# B311D.net
KiCad netlist of a schematic drawn in EAGLE
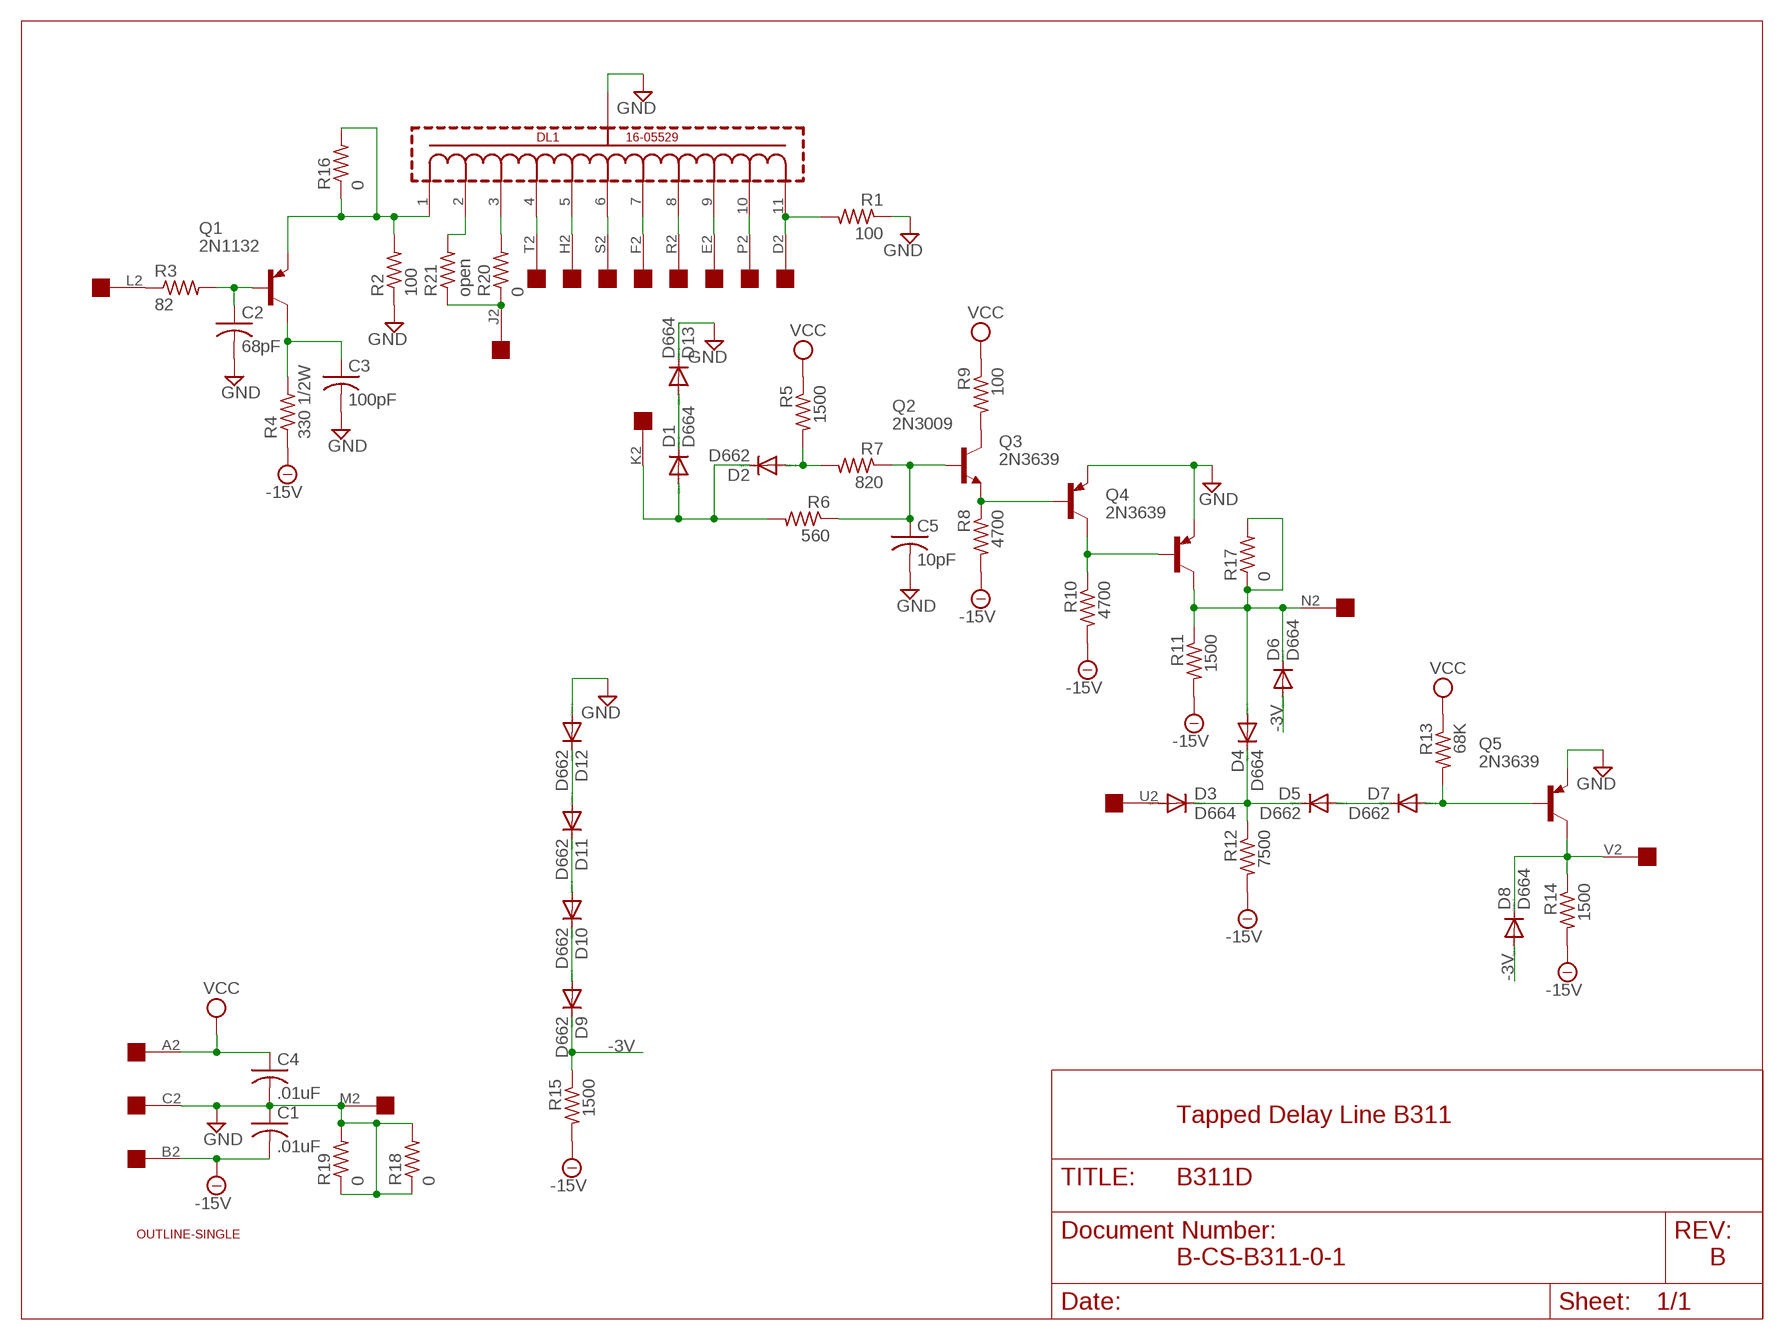
[diagram p0: schematic, sheet 1]

(export (version "E")
  (design (tool "Eeschema 10.0.6"))
  (components
    (comp (ref "C1")
      (value ".01uF")
      (footprint "eagle-import:C063-025X075")
      (libsource (lib "eagle-import") (part "C-US"))
    )
    (comp (ref "C2")
      (value "68pF")
      (footprint "eagle-import:C063-025X075")
      (libsource (lib "eagle-import") (part "C-US"))
    )
    (comp (ref "C3")
      (value "100pF")
      (footprint "eagle-import:C063-025X075")
      (libsource (lib "eagle-import") (part "C-US"))
    )
    (comp (ref "C4")
      (value ".01uF")
      (footprint "eagle-import:C063-025X075")
      (libsource (lib "eagle-import") (part "C-US"))
    )
    (comp (ref "C5")
      (value "10pF")
      (footprint "eagle-import:C063-025X075")
      (libsource (lib "eagle-import") (part "C-US"))
    )
    (comp (ref "D1")
      (value "D664")
      (footprint "eagle-import:DO35-10")
      (libsource (lib "eagle-import") (part "DIODE-DO35-10"))
    )
    (comp (ref "D2")
      (value "D662")
      (footprint "eagle-import:DO35-10")
      (libsource (lib "eagle-import") (part "DIODE-DO35-10"))
    )
    (comp (ref "D3")
      (value "D664")
      (footprint "eagle-import:DO35-10")
      (libsource (lib "eagle-import") (part "DIODE-DO35-10"))
    )
    (comp (ref "D4")
      (value "D664")
      (footprint "eagle-import:DO35-10")
      (libsource (lib "eagle-import") (part "DIODE-DO35-10"))
    )
    (comp (ref "D5")
      (value "D662")
      (footprint "eagle-import:DO35-10")
      (libsource (lib "eagle-import") (part "DIODE-DO35-10"))
    )
    (comp (ref "D6")
      (value "D664")
      (footprint "eagle-import:DO35-10")
      (libsource (lib "eagle-import") (part "DIODE-DO35-10"))
    )
    (comp (ref "D7")
      (value "D662")
      (footprint "eagle-import:DO35-10")
      (libsource (lib "eagle-import") (part "DIODE-DO35-10"))
    )
    (comp (ref "D8")
      (value "D664")
      (footprint "eagle-import:DO35-10")
      (libsource (lib "eagle-import") (part "DIODE-DO35-10"))
    )
    (comp (ref "D9")
      (value "D662")
      (footprint "eagle-import:DO35-10")
      (libsource (lib "eagle-import") (part "DIODE-DO35-10"))
    )
    (comp (ref "D10")
      (value "D662")
      (footprint "eagle-import:DO35-10")
      (libsource (lib "eagle-import") (part "DIODE-DO35-10"))
    )
    (comp (ref "D11")
      (value "D662")
      (footprint "eagle-import:DO35-10")
      (libsource (lib "eagle-import") (part "DIODE-DO35-10"))
    )
    (comp (ref "D12")
      (value "D662")
      (footprint "eagle-import:DO35-10")
      (libsource (lib "eagle-import") (part "DIODE-DO35-10"))
    )
    (comp (ref "D13")
      (value "D664")
      (footprint "eagle-import:DO35-10")
      (libsource (lib "eagle-import") (part "DIODE-DO35-10"))
    )
    (comp (ref "DL1")
      (value "16-05529")
      (footprint "eagle-import:16-05529")
      (libsource (lib "eagle-import") (part "16-05529"))
    )
    (comp (ref "Q1")
      (value "2N1132")
      (footprint "eagle-import:TO5")
      (libsource (lib "eagle-import") (part "-PNP-TO5"))
    )
    (comp (ref "Q2")
      (value "2N3009")
      (footprint "eagle-import:TO5")
      (libsource (lib "eagle-import") (part "-NPN-TO5"))
    )
    (comp (ref "Q3")
      (value "2N3639")
      (footprint "eagle-import:TO5")
      (libsource (lib "eagle-import") (part "-PNP-TO5"))
    )
    (comp (ref "Q4")
      (value "2N3639")
      (footprint "eagle-import:TO5")
      (libsource (lib "eagle-import") (part "-PNP-TO5"))
    )
    (comp (ref "Q5")
      (value "2N3639")
      (footprint "eagle-import:TO5")
      (libsource (lib "eagle-import") (part "-PNP-TO5"))
    )
    (comp (ref "R1")
      (value "100")
      (footprint "eagle-import:0207_10")
      (libsource (lib "eagle-import") (part "R-US_0207/10"))
    )
    (comp (ref "R2")
      (value "100")
      (footprint "eagle-import:0207_10")
      (libsource (lib "eagle-import") (part "R-US_0207/10"))
    )
    (comp (ref "R3")
      (value "82")
      (footprint "eagle-import:0207_10")
      (libsource (lib "eagle-import") (part "R-US_0207/10"))
    )
    (comp (ref "R4")
      (value "330 1/2W")
      (footprint "eagle-import:0411_15")
      (libsource (lib "eagle-import") (part "R-US_0411/15"))
    )
    (comp (ref "R5")
      (value "1500")
      (footprint "eagle-import:0207_10")
      (libsource (lib "eagle-import") (part "R-US_0207/10"))
    )
    (comp (ref "R6")
      (value "560")
      (footprint "eagle-import:0207_10")
      (libsource (lib "eagle-import") (part "R-US_0207/10"))
    )
    (comp (ref "R7")
      (value "820")
      (footprint "eagle-import:0207_10")
      (libsource (lib "eagle-import") (part "R-US_0207/10"))
    )
    (comp (ref "R8")
      (value "4700")
      (footprint "eagle-import:0207_10")
      (libsource (lib "eagle-import") (part "R-US_0207/10"))
    )
    (comp (ref "R9")
      (value "100")
      (footprint "eagle-import:0207_10")
      (libsource (lib "eagle-import") (part "R-US_0207/10"))
    )
    (comp (ref "R10")
      (value "4700")
      (footprint "eagle-import:0207_10")
      (libsource (lib "eagle-import") (part "R-US_0207/10"))
    )
    (comp (ref "R11")
      (value "1500")
      (footprint "eagle-import:0207_10")
      (libsource (lib "eagle-import") (part "R-US_0207/10"))
    )
    (comp (ref "R12")
      (value "7500")
      (footprint "eagle-import:0207_10")
      (libsource (lib "eagle-import") (part "R-US_0207/10"))
    )
    (comp (ref "R13")
      (value "68K")
      (footprint "eagle-import:0207_10")
      (libsource (lib "eagle-import") (part "R-US_0207/10"))
    )
    (comp (ref "R14")
      (value "1500")
      (footprint "eagle-import:0207_10")
      (libsource (lib "eagle-import") (part "R-US_0207/10"))
    )
    (comp (ref "R15")
      (value "1500")
      (footprint "eagle-import:0207_10")
      (libsource (lib "eagle-import") (part "R-US_0207/10"))
    )
    (comp (ref "R16")
      (value "0")
      (footprint "eagle-import:0207_10")
      (libsource (lib "eagle-import") (part "R-US_0207/10"))
    )
    (comp (ref "R17")
      (value "0")
      (footprint "eagle-import:0207_10")
      (libsource (lib "eagle-import") (part "R-US_0207/10"))
    )
    (comp (ref "R18")
      (value "0")
      (footprint "eagle-import:0207_10")
      (libsource (lib "eagle-import") (part "R-US_0207/10"))
    )
    (comp (ref "R19")
      (value "0")
      (footprint "eagle-import:0207_10")
      (libsource (lib "eagle-import") (part "R-US_0207/10"))
    )
    (comp (ref "R20")
      (value "0")
      (footprint "eagle-import:0207_10")
      (libsource (lib "eagle-import") (part "R-US_0207/10"))
    )
    (comp (ref "R21")
      (value "open")
      (footprint "eagle-import:0207_10")
      (libsource (lib "eagle-import") (part "R-US_0207/10"))
    )
    (comp (ref "U$1")
      (value "OUTLINE-SINGLE")
      (footprint "eagle-import:SINGLE")
      (libsource (lib "eagle-import") (part "OUTLINE-SINGLE"))
    )
    (comp (ref "U$2")
      (value "EDGE-1")
      (footprint "eagle-import:EDGE-CON1")
      (libsource (lib "eagle-import") (part "EDGE-1"))
    )
  )
  (nets
    (net (code "1") (name "-15V") (class "Default")
      (node (ref "C1") (pin "2") (pinfunction "2_2") (pintype "passive"))
      (node (ref "R10") (pin "2") (pinfunction "2_2") (pintype "passive"))
      (node (ref "R11") (pin "2") (pinfunction "2_2") (pintype "passive"))
      (node (ref "R12") (pin "2") (pinfunction "2_2") (pintype "passive"))
      (node (ref "R14") (pin "2") (pinfunction "2_2") (pintype "passive"))
      (node (ref "R15") (pin "2") (pinfunction "2_2") (pintype "passive"))
      (node (ref "R4") (pin "1") (pinfunction "1_1") (pintype "passive"))
      (node (ref "R8") (pin "2") (pinfunction "2_2") (pintype "passive"))
      (node (ref "U$2") (pin "B2") (pinfunction "1_B2") (pintype "bidirectional"))
    )
    (net (code "2") (name "/-3V") (class "Default")
      (node (ref "D6") (pin "A") (pinfunction "A_A") (pintype "passive"))
      (node (ref "D8") (pin "A") (pinfunction "A_A") (pintype "passive"))
      (node (ref "D9") (pin "C") (pinfunction "C_C") (pintype "passive"))
      (node (ref "R15") (pin "1") (pinfunction "1_1") (pintype "passive"))
    )
    (net (code "3") (name "GND") (class "Default")
      (node (ref "C1") (pin "1") (pinfunction "1_1") (pintype "passive"))
      (node (ref "C2") (pin "2") (pinfunction "2_2") (pintype "passive"))
      (node (ref "C3") (pin "2") (pinfunction "2_2") (pintype "passive"))
      (node (ref "C4") (pin "2") (pinfunction "2_2") (pintype "passive"))
      (node (ref "C5") (pin "2") (pinfunction "2_2") (pintype "passive"))
      (node (ref "D12") (pin "A") (pinfunction "A_A") (pintype "passive"))
      (node (ref "D13") (pin "C") (pinfunction "C_C") (pintype "passive"))
      (node (ref "DL1") (pin "12") (pinfunction "GND_12") (pintype "passive"))
      (node (ref "Q3") (pin "1") (pinfunction "E_1") (pintype "passive"))
      (node (ref "Q4") (pin "1") (pinfunction "E_1") (pintype "passive"))
      (node (ref "Q5") (pin "1") (pinfunction "E_1") (pintype "passive"))
      (node (ref "R1") (pin "1") (pinfunction "1_1") (pintype "passive"))
      (node (ref "R18") (pin "1") (pinfunction "1_1") (pintype "passive"))
      (node (ref "R18") (pin "2") (pinfunction "2_2") (pintype "passive"))
      (node (ref "R19") (pin "1") (pinfunction "1_1") (pintype "passive"))
      (node (ref "R19") (pin "2") (pinfunction "2_2") (pintype "passive"))
      (node (ref "R2") (pin "1") (pinfunction "1_1") (pintype "passive"))
      (node (ref "U$2") (pin "C2") (pinfunction "1_C2") (pintype "bidirectional"))
      (node (ref "U$2") (pin "M2") (pinfunction "1_M2") (pintype "bidirectional"))
    )
    (net (code "4") (name "Net-(D1-PadC)") (class "Default")
      (node (ref "D1") (pin "C") (pinfunction "C_C") (pintype "passive"))
      (node (ref "D13") (pin "A") (pinfunction "A_A") (pintype "passive"))
    )
    (net (code "5") (name "Net-(D2-PadA)") (class "Default")
      (node (ref "D2") (pin "A") (pinfunction "A_A") (pintype "passive"))
      (node (ref "R5") (pin "2") (pinfunction "2_2") (pintype "passive"))
      (node (ref "R7") (pin "2") (pinfunction "2_2") (pintype "passive"))
    )
    (net (code "6") (name "Net-(D3-PadC)") (class "Default")
      (node (ref "D3") (pin "C") (pinfunction "C_C") (pintype "passive"))
      (node (ref "D4") (pin "C") (pinfunction "C_C") (pintype "passive"))
      (node (ref "D5") (pin "C") (pinfunction "C_C") (pintype "passive"))
      (node (ref "R12") (pin "1") (pinfunction "1_1") (pintype "passive"))
    )
    (net (code "7") (name "Net-(D5-PadA)") (class "Default")
      (node (ref "D5") (pin "A") (pinfunction "A_A") (pintype "passive"))
      (node (ref "D7") (pin "C") (pinfunction "C_C") (pintype "passive"))
    )
    (net (code "8") (name "Net-(D10-PadA)") (class "Default")
      (node (ref "D10") (pin "A") (pinfunction "A_A") (pintype "passive"))
      (node (ref "D11") (pin "C") (pinfunction "C_C") (pintype "passive"))
    )
    (net (code "9") (name "Net-(D10-PadC)") (class "Default")
      (node (ref "D10") (pin "C") (pinfunction "C_C") (pintype "passive"))
      (node (ref "D9") (pin "A") (pinfunction "A_A") (pintype "passive"))
    )
    (net (code "10") (name "Net-(D11-PadA)") (class "Default")
      (node (ref "D11") (pin "A") (pinfunction "A_A") (pintype "passive"))
      (node (ref "D12") (pin "C") (pinfunction "C_C") (pintype "passive"))
    )
    (net (code "11") (name "Net-(DL1-0)") (class "Default")
      (node (ref "DL1") (pin "1") (pinfunction "0_1") (pintype "passive"))
      (node (ref "Q1") (pin "1") (pinfunction "E_1") (pintype "passive"))
      (node (ref "R16") (pin "1") (pinfunction "1_1") (pintype "passive"))
      (node (ref "R16") (pin "2") (pinfunction "2_2") (pintype "passive"))
      (node (ref "R2") (pin "2") (pinfunction "2_2") (pintype "passive"))
    )
    (net (code "12") (name "Net-(DL1-5)") (class "Default")
      (node (ref "DL1") (pin "2") (pinfunction "5_2") (pintype "passive"))
      (node (ref "R21") (pin "2") (pinfunction "2_2") (pintype "passive"))
    )
    (net (code "13") (name "Net-(DL1-10)") (class "Default")
      (node (ref "DL1") (pin "3") (pinfunction "10_3") (pintype "passive"))
      (node (ref "R20") (pin "2") (pinfunction "2_2") (pintype "passive"))
    )
    (net (code "14") (name "Net-(DL1-15)") (class "Default")
      (node (ref "DL1") (pin "4") (pinfunction "15_4") (pintype "passive"))
      (node (ref "U$2") (pin "T2") (pinfunction "1_T2") (pintype "bidirectional"))
    )
    (net (code "15") (name "Net-(DL1-20)") (class "Default")
      (node (ref "DL1") (pin "5") (pinfunction "20_5") (pintype "passive"))
      (node (ref "U$2") (pin "H2") (pinfunction "1_H2") (pintype "bidirectional"))
    )
    (net (code "16") (name "Net-(DL1-25)") (class "Default")
      (node (ref "DL1") (pin "6") (pinfunction "25_6") (pintype "passive"))
      (node (ref "U$2") (pin "S2") (pinfunction "1_S2") (pintype "bidirectional"))
    )
    (net (code "17") (name "Net-(DL1-30)") (class "Default")
      (node (ref "DL1") (pin "7") (pinfunction "30_7") (pintype "passive"))
      (node (ref "U$2") (pin "F2") (pinfunction "1_F2") (pintype "bidirectional"))
    )
    (net (code "18") (name "Net-(DL1-35)") (class "Default")
      (node (ref "DL1") (pin "8") (pinfunction "35_8") (pintype "passive"))
      (node (ref "U$2") (pin "R2") (pinfunction "1_R2") (pintype "bidirectional"))
    )
    (net (code "19") (name "Net-(DL1-40)") (class "Default")
      (node (ref "DL1") (pin "9") (pinfunction "40_9") (pintype "passive"))
      (node (ref "U$2") (pin "E2") (pinfunction "1_E2") (pintype "bidirectional"))
    )
    (net (code "20") (name "Net-(DL1-45)") (class "Default")
      (node (ref "DL1") (pin "10") (pinfunction "45_10") (pintype "passive"))
      (node (ref "U$2") (pin "P2") (pinfunction "1_P2") (pintype "bidirectional"))
    )
    (net (code "21") (name "Net-(DL1-50)") (class "Default")
      (node (ref "DL1") (pin "11") (pinfunction "50_11") (pintype "passive"))
      (node (ref "R1") (pin "2") (pinfunction "2_2") (pintype "passive"))
      (node (ref "U$2") (pin "D2") (pinfunction "1_D2") (pintype "bidirectional"))
    )
    (net (code "22") (name "Net-(Q1-B)") (class "Default")
      (node (ref "C2") (pin "1") (pinfunction "1_1") (pintype "passive"))
      (node (ref "Q1") (pin "2") (pinfunction "B_2") (pintype "passive"))
      (node (ref "R3") (pin "2") (pinfunction "2_2") (pintype "passive"))
    )
    (net (code "23") (name "Net-(Q1-C)") (class "Default")
      (node (ref "C3") (pin "1") (pinfunction "1_1") (pintype "passive"))
      (node (ref "Q1") (pin "3") (pinfunction "C_3") (pintype "passive"))
      (node (ref "R4") (pin "2") (pinfunction "2_2") (pintype "passive"))
    )
    (net (code "24") (name "Net-(Q2-B)") (class "Default")
      (node (ref "C5") (pin "1") (pinfunction "1_1") (pintype "passive"))
      (node (ref "Q2") (pin "2") (pinfunction "B_2") (pintype "passive"))
      (node (ref "R6") (pin "1") (pinfunction "1_1") (pintype "passive"))
      (node (ref "R7") (pin "1") (pinfunction "1_1") (pintype "passive"))
    )
    (net (code "25") (name "Net-(Q2-C)") (class "Default")
      (node (ref "Q2") (pin "3") (pinfunction "C_3") (pintype "passive"))
      (node (ref "R9") (pin "2") (pinfunction "2_2") (pintype "passive"))
    )
    (net (code "26") (name "Net-(Q2-E)") (class "Default")
      (node (ref "Q2") (pin "1") (pinfunction "E_1") (pintype "passive"))
      (node (ref "Q3") (pin "2") (pinfunction "B_2") (pintype "passive"))
      (node (ref "R8") (pin "1") (pinfunction "1_1") (pintype "passive"))
    )
    (net (code "27") (name "Net-(Q3-C)") (class "Default")
      (node (ref "Q3") (pin "3") (pinfunction "C_3") (pintype "passive"))
      (node (ref "Q4") (pin "2") (pinfunction "B_2") (pintype "passive"))
      (node (ref "R10") (pin "1") (pinfunction "1_1") (pintype "passive"))
    )
    (net (code "28") (name "Net-(Q4-C)") (class "Default")
      (node (ref "D4") (pin "A") (pinfunction "A_A") (pintype "passive"))
      (node (ref "D6") (pin "C") (pinfunction "C_C") (pintype "passive"))
      (node (ref "Q4") (pin "3") (pinfunction "C_3") (pintype "passive"))
      (node (ref "R11") (pin "1") (pinfunction "1_1") (pintype "passive"))
      (node (ref "R17") (pin "1") (pinfunction "1_1") (pintype "passive"))
      (node (ref "R17") (pin "2") (pinfunction "2_2") (pintype "passive"))
      (node (ref "U$2") (pin "N2") (pinfunction "1_N2") (pintype "bidirectional"))
    )
    (net (code "29") (name "Net-(Q5-B)") (class "Default")
      (node (ref "D7") (pin "A") (pinfunction "A_A") (pintype "passive"))
      (node (ref "Q5") (pin "2") (pinfunction "B_2") (pintype "passive"))
      (node (ref "R13") (pin "2") (pinfunction "2_2") (pintype "passive"))
    )
    (net (code "30") (name "Net-(Q5-C)") (class "Default")
      (node (ref "D8") (pin "C") (pinfunction "C_C") (pintype "passive"))
      (node (ref "Q5") (pin "3") (pinfunction "C_3") (pintype "passive"))
      (node (ref "R14") (pin "1") (pinfunction "1_1") (pintype "passive"))
      (node (ref "U$2") (pin "V2") (pinfunction "1_V2") (pintype "bidirectional"))
    )
    (net (code "31") (name "Net-(U$2H-1)") (class "Default")
      (node (ref "R20") (pin "1") (pinfunction "1_1") (pintype "passive"))
      (node (ref "R21") (pin "1") (pinfunction "1_1") (pintype "passive"))
      (node (ref "U$2") (pin "J2") (pinfunction "1_J2") (pintype "bidirectional"))
    )
    (net (code "32") (name "Net-(U$2I-1)") (class "Default")
      (node (ref "D1") (pin "A") (pinfunction "A_A") (pintype "passive"))
      (node (ref "D2") (pin "C") (pinfunction "C_C") (pintype "passive"))
      (node (ref "R6") (pin "2") (pinfunction "2_2") (pintype "passive"))
      (node (ref "U$2") (pin "K2") (pinfunction "1_K2") (pintype "bidirectional"))
    )
    (net (code "33") (name "Net-(U$2J-1)") (class "Default")
      (node (ref "R3") (pin "1") (pinfunction "1_1") (pintype "passive"))
      (node (ref "U$2") (pin "L2") (pinfunction "1_L2") (pintype "bidirectional"))
    )
    (net (code "34") (name "Net-(U$2Q-1)") (class "Default")
      (node (ref "D3") (pin "A") (pinfunction "A_A") (pintype "passive"))
      (node (ref "U$2") (pin "U2") (pinfunction "1_U2") (pintype "bidirectional"))
    )
    (net (code "35") (name "VCC") (class "Default")
      (node (ref "C4") (pin "1") (pinfunction "1_1") (pintype "passive"))
      (node (ref "R13") (pin "1") (pinfunction "1_1") (pintype "passive"))
      (node (ref "R5") (pin "1") (pinfunction "1_1") (pintype "passive"))
      (node (ref "R9") (pin "1") (pinfunction "1_1") (pintype "passive"))
      (node (ref "U$2") (pin "A2") (pinfunction "1_A2") (pintype "bidirectional"))
    )
  )
)
